# Schematic.net
KiCad netlist of a schematic drawn in Altium Designer
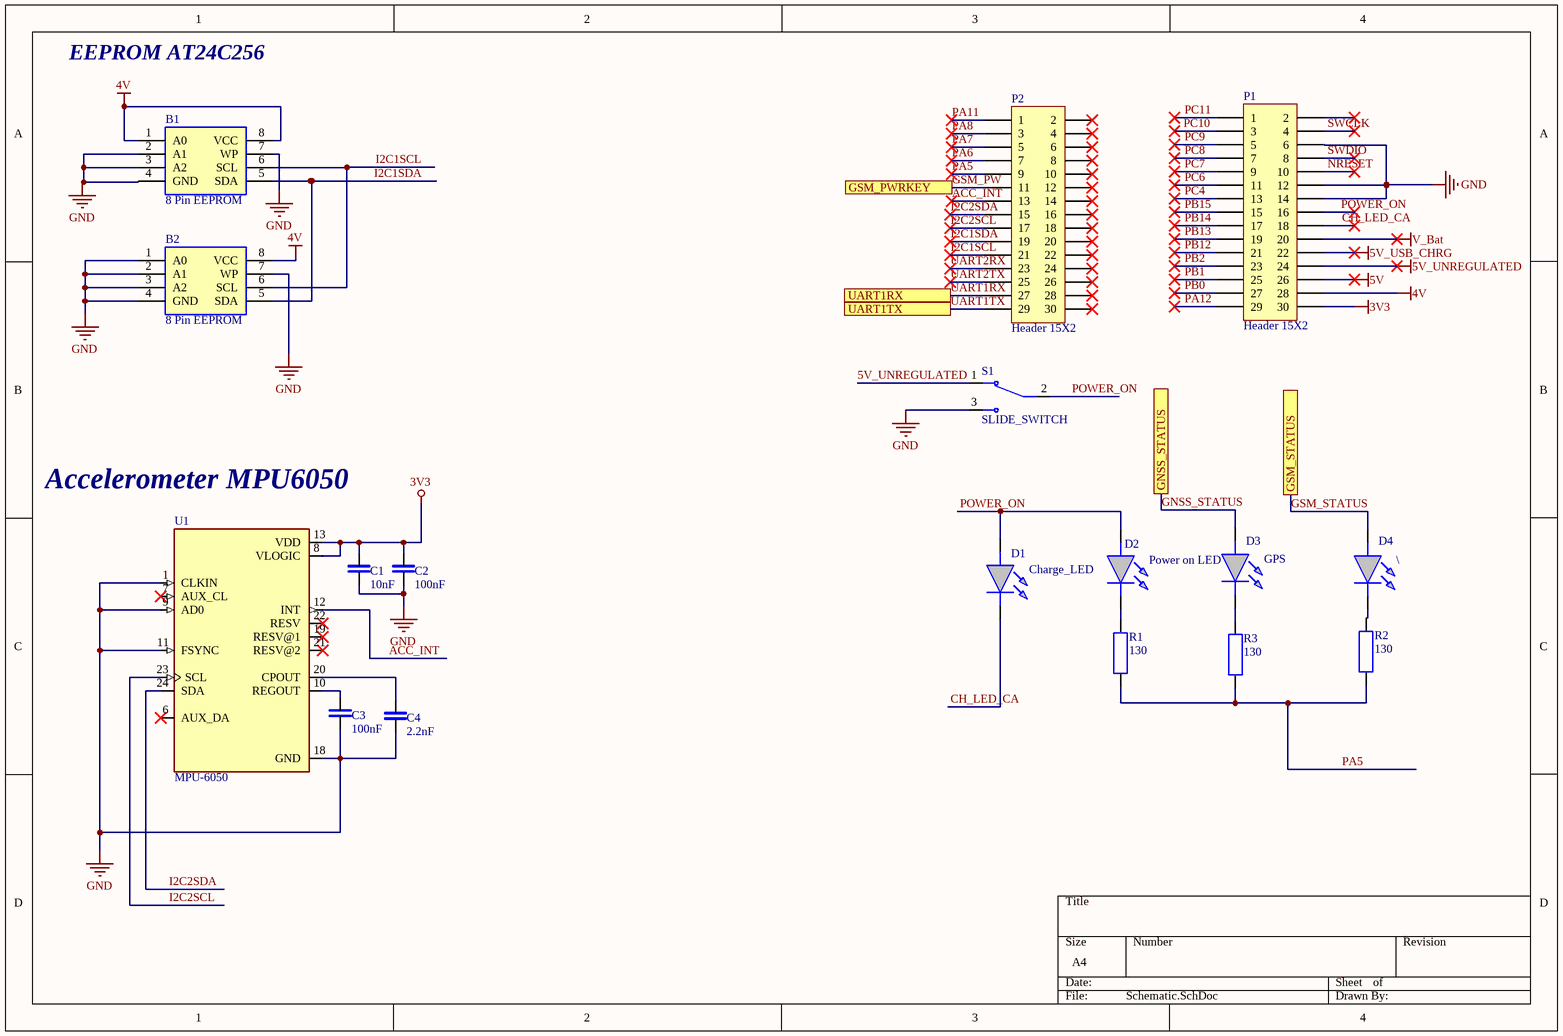
[diagram p0: Schematic.SchDoc]

(export (version "E")
  (design (tool "Eeschema 10.0.6"))
  (components
    (comp (ref "B1")
      (value "8 Pin EEPROM")
      (footprint "AT24C256")
      (fields
        (field (name "MANUFACTURER_PART_NUMBER") "AT24C256C-SSHL-T")
        (field (name "MOUSER PART NUMBER") "556-AT24C256C-SSHL-T")
      )
      (libsource (lib "IC") (part "AT24C256C"))
    )
    (comp (ref "B2")
      (value "8 Pin EEPROM")
      (footprint "AT24C256")
      (fields
        (field (name "MANUFACTURER_PART_NUMBER") "AT24C256C-SSHL-T")
        (field (name "MOUSER PART NUMBER") "556-AT24C256C-SSHL-T")
      )
      (libsource (lib "IC") (part "AT24C256C"))
    )
    (comp (ref "C1")
      (value "10nF")
      (footprint "CAP_0805")
      (fields (field (name "MP") "LD051A270KAB2A"))
      (libsource (lib "Passive_Components") (part "SMT_CAP"))
    )
    (comp (ref "C2")
      (value "100nF")
      (footprint "CAP_0805")
      (fields (field (name "MP") "LD051A270KAB2A"))
      (libsource (lib "Passive_Components") (part "SMT_CAP"))
    )
    (comp (ref "C3")
      (value "100nF")
      (footprint "CAP_0805")
      (fields (field (name "MP") "LD051A270KAB2A"))
      (libsource (lib "Passive_Components") (part "SMT_CAP"))
    )
    (comp (ref "C4")
      (value "2.2nF")
      (footprint "CAP_0805")
      (fields (field (name "MP") "LD051A270KAB2A"))
      (libsource (lib "Passive_Components") (part "SMT_CAP"))
    )
    (comp (ref "D1")
      (value "Charge_LED")
      (footprint "LED_0805")
      (fields
        (field (name "MANUFACTURER_PART_NUMBER") "HSMH-C170")
        (field (name "MOUSER PART NUMBER") "630-HSMH-C170")
      )
      (libsource (lib "Diodes") (part "LED"))
    )
    (comp (ref "D2")
      (value "Power on LED")
      (footprint "LED_0805")
      (fields
        (field (name "MANUFACTURER_PART_NUMBER") "HSMH-C170")
        (field (name "MOUSER PART NUMBER") "630-HSMH-C170")
      )
      (libsource (lib "Diodes") (part "LED"))
    )
    (comp (ref "D3")
      (value "GPS")
      (footprint "LED_0805")
      (fields
        (field (name "MANUFACTURER_PART_NUMBER") "HSMH-C170")
        (field (name "MOUSER PART NUMBER") "630-HSMH-C170")
      )
      (libsource (lib "Diodes") (part "LED"))
    )
    (comp (ref "D4")
      (value "\\")
      (footprint "LED_0805")
      (fields
        (field (name "MANUFACTURER_PART_NUMBER") "HSMH-C170")
        (field (name "MOUSER PART NUMBER") "630-HSMH-C170")
      )
      (libsource (lib "Diodes") (part "LED"))
    )
    (comp (ref "P1")
      (value "Header 15X2")
      (footprint "HDR2X15")
      (description "Header, 15-Pin, Dual row")
      (fields (field (name "PUBLISHER") "Altium Limited"))
      (libsource (lib "Miscellaneous Connectors") (part "Header 15X2"))
    )
    (comp (ref "P2")
      (value "Header 15X2")
      (footprint "HDR2X15")
      (description "Header, 15-Pin, Dual row")
      (fields (field (name "PUBLISHER") "Altium Limited"))
      (libsource (lib "Miscellaneous Connectors") (part "Header 15X2"))
    )
    (comp (ref "R1")
      (value "130")
      (footprint "RES_0805")
      (fields
        (field (name "MP") "2-2176053-0")
        (field (name "TOLERANCE") "1%")
        (field (name "MF") "TE Connectivity")
      )
      (libsource (lib "Passive_Components") (part "SMT_RES"))
    )
    (comp (ref "R2")
      (value "130")
      (footprint "RES_0805")
      (fields
        (field (name "MP") "2-2176053-0")
        (field (name "TOLERANCE") "1%")
        (field (name "MF") "TE Connectivity")
      )
      (libsource (lib "Passive_Components") (part "SMT_RES"))
    )
    (comp (ref "R3")
      (value "130")
      (footprint "RES_0805")
      (fields
        (field (name "MP") "2-2176053-0")
        (field (name "TOLERANCE") "1%")
        (field (name "MF") "TE Connectivity")
      )
      (libsource (lib "Passive_Components") (part "SMT_RES"))
    )
    (comp (ref "S1")
      (value "SLIDE_SWITCH")
      (footprint "SLIDE_SWITCH_BIG")
      (fields (field (name "MP") "500SSP1S2M2QEA"))
      (libsource (lib "Extras") (part "SLIDE_SWITCH_BIG"))
    )
    (comp (ref "U1")
      (value "MPU-6050")
      (footprint "MPU_6050")
      (fields (field (name "MF") "TDK InvenSense"))
      (libsource (lib "IC") (part "MPU-6050"))
    )
  )
  (nets
    (net (code "2") (name "/ACC_INT") (class "Default")
      (node (ref "P2") (pin "13") (pinfunction "13_13") (pintype "passive"))
      (node (ref "U1") (pin "12") (pinfunction "INT_12") (pintype "output"))
    )
    (net (code "3") (name "/CH_LED_CA") (class "Default")
      (node (ref "D1") (pin "1") (pinfunction "K_1") (pintype "passive"))
      (node (ref "P1") (pin "18") (pinfunction "18_18") (pintype "passive"))
    )
    (net (code "4") (name "/GNSS_STATUS") (class "Default")
      (node (ref "D3") (pin "2") (pinfunction "A_2") (pintype "passive"))
    )
    (net (code "5") (name "/GSM_PW") (class "Default")
      (node (ref "P2") (pin "11") (pinfunction "11_11") (pintype "passive"))
    )
    (net (code "6") (name "/GSM_STATUS") (class "Default")
      (node (ref "D4") (pin "2") (pinfunction "A_2") (pintype "passive"))
    )
    (net (code "7") (name "/I2C1SCL") (class "Default")
      (node (ref "B1") (pin "6") (pinfunction "SCL_6") (pintype "passive"))
      (node (ref "B2") (pin "6") (pinfunction "SCL_6") (pintype "passive"))
      (node (ref "P2") (pin "21") (pinfunction "21_21") (pintype "passive"))
    )
    (net (code "8") (name "/I2C1SDA") (class "Default")
      (node (ref "B1") (pin "5") (pinfunction "SDA_5") (pintype "passive"))
      (node (ref "B2") (pin "5") (pinfunction "SDA_5") (pintype "passive"))
      (node (ref "P2") (pin "19") (pinfunction "19_19") (pintype "passive"))
    )
    (net (code "9") (name "/I2C2SCL") (class "Default")
      (node (ref "P2") (pin "17") (pinfunction "17_17") (pintype "passive"))
      (node (ref "U1") (pin "23") (pinfunction "SCL_23") (pintype "input"))
    )
    (net (code "10") (name "/I2C2SDA") (class "Default")
      (node (ref "P2") (pin "15") (pinfunction "15_15") (pintype "passive"))
      (node (ref "U1") (pin "24") (pinfunction "SDA_24") (pintype "bidirectional"))
    )
    (net (code "11") (name "/NRESET") (class "Default")
      (node (ref "P1") (pin "10") (pinfunction "10_10") (pintype "passive+no_connect"))
    )
    (net (code "12") (name "/PA5") (class "Default")
      (node (ref "P2") (pin "9") (pinfunction "9_9") (pintype "passive"))
      (node (ref "R1") (pin "1") (pinfunction "1_1") (pintype "passive"))
      (node (ref "R2") (pin "1") (pinfunction "1_1") (pintype "passive"))
      (node (ref "R3") (pin "1") (pinfunction "1_1") (pintype "passive"))
    )
    (net (code "13") (name "/PA6") (class "Default")
      (node (ref "P2") (pin "7") (pinfunction "7_7") (pintype "passive+no_connect"))
    )
    (net (code "14") (name "/PA7") (class "Default")
      (node (ref "P2") (pin "5") (pinfunction "5_5") (pintype "passive+no_connect"))
    )
    (net (code "15") (name "/PA8") (class "Default")
      (node (ref "P2") (pin "3") (pinfunction "3_3") (pintype "passive+no_connect"))
    )
    (net (code "16") (name "/PA11") (class "Default")
      (node (ref "P2") (pin "1") (pinfunction "1_1") (pintype "passive+no_connect"))
    )
    (net (code "17") (name "/PA12") (class "Default")
      (node (ref "P1") (pin "29") (pinfunction "29_29") (pintype "passive+no_connect"))
    )
    (net (code "18") (name "/PB0") (class "Default")
      (node (ref "P1") (pin "27") (pinfunction "27_27") (pintype "passive+no_connect"))
    )
    (net (code "19") (name "/PB1") (class "Default")
      (node (ref "P1") (pin "25") (pinfunction "25_25") (pintype "passive+no_connect"))
    )
    (net (code "20") (name "/PB2") (class "Default")
      (node (ref "P1") (pin "23") (pinfunction "23_23") (pintype "passive+no_connect"))
    )
    (net (code "21") (name "/PB12") (class "Default")
      (node (ref "P1") (pin "21") (pinfunction "21_21") (pintype "passive+no_connect"))
    )
    (net (code "22") (name "/PB13") (class "Default")
      (node (ref "P1") (pin "19") (pinfunction "19_19") (pintype "passive+no_connect"))
    )
    (net (code "23") (name "/PB14") (class "Default")
      (node (ref "P1") (pin "17") (pinfunction "17_17") (pintype "passive+no_connect"))
    )
    (net (code "24") (name "/PB15") (class "Default")
      (node (ref "P1") (pin "15") (pinfunction "15_15") (pintype "passive+no_connect"))
    )
    (net (code "25") (name "/PC4") (class "Default")
      (node (ref "P1") (pin "13") (pinfunction "13_13") (pintype "passive+no_connect"))
    )
    (net (code "26") (name "/PC6") (class "Default")
      (node (ref "P1") (pin "11") (pinfunction "11_11") (pintype "passive+no_connect"))
    )
    (net (code "27") (name "/PC7") (class "Default")
      (node (ref "P1") (pin "9") (pinfunction "9_9") (pintype "passive+no_connect"))
    )
    (net (code "28") (name "/PC8") (class "Default")
      (node (ref "P1") (pin "7") (pinfunction "7_7") (pintype "passive+no_connect"))
    )
    (net (code "29") (name "/PC9") (class "Default")
      (node (ref "P1") (pin "5") (pinfunction "5_5") (pintype "passive+no_connect"))
    )
    (net (code "30") (name "/PC10") (class "Default")
      (node (ref "P1") (pin "3") (pinfunction "3_3") (pintype "passive+no_connect"))
    )
    (net (code "31") (name "/PC11") (class "Default")
      (node (ref "P1") (pin "1") (pinfunction "1_1") (pintype "passive+no_connect"))
    )
    (net (code "32") (name "/POWER_ON") (class "Default")
      (node (ref "D1") (pin "2") (pinfunction "A_2") (pintype "passive"))
      (node (ref "D2") (pin "2") (pinfunction "A_2") (pintype "passive"))
      (node (ref "P1") (pin "16") (pinfunction "16_16") (pintype "passive"))
      (node (ref "S1") (pin "2") (pinfunction "COM_2") (pintype "passive"))
    )
    (net (code "33") (name "/SWCLK") (class "Default")
      (node (ref "P1") (pin "4") (pinfunction "4_4") (pintype "passive+no_connect"))
    )
    (net (code "34") (name "/SWDIO") (class "Default")
      (node (ref "P1") (pin "8") (pinfunction "8_8") (pintype "passive+no_connect"))
    )
    (net (code "35") (name "/UART1RX") (class "Default")
      (node (ref "P2") (pin "27") (pinfunction "27_27") (pintype "passive"))
    )
    (net (code "36") (name "/UART1TX") (class "Default")
      (node (ref "P2") (pin "29") (pinfunction "29_29") (pintype "passive"))
    )
    (net (code "37") (name "/UART2RX") (class "Default")
      (node (ref "P2") (pin "23") (pinfunction "23_23") (pintype "passive+no_connect"))
    )
    (net (code "38") (name "/UART2TX") (class "Default")
      (node (ref "P2") (pin "25") (pinfunction "25_25") (pintype "passive+no_connect"))
    )
    (net (code "39") (name "3V3") (class "Default")
      (node (ref "C1") (pin "2") (pinfunction "2_2") (pintype "passive"))
      (node (ref "C2") (pin "2") (pinfunction "2_2") (pintype "passive"))
      (node (ref "P1") (pin "30") (pinfunction "30_30") (pintype "passive"))
      (node (ref "U1") (pin "13") (pinfunction "VDD_13") (pintype "power_in"))
      (node (ref "U1") (pin "8") (pinfunction "VLOGIC_8") (pintype "power_in"))
    )
    (net (code "40") (name "4V") (class "Default")
      (node (ref "B1") (pin "1") (pinfunction "A0_1") (pintype "passive"))
      (node (ref "B1") (pin "8") (pinfunction "VCC_8") (pintype "passive"))
      (node (ref "B2") (pin "8") (pinfunction "VCC_8") (pintype "passive"))
      (node (ref "P1") (pin "28") (pinfunction "28_28") (pintype "passive"))
    )
    (net (code "41") (name "5V") (class "Default")
      (node (ref "P1") (pin "26") (pinfunction "26_26") (pintype "passive"))
    )
    (net (code "42") (name "5V_UNREGULATED") (class "Default")
      (node (ref "P1") (pin "24") (pinfunction "24_24") (pintype "passive"))
      (node (ref "S1") (pin "1") (pinfunction "NC_1") (pintype "passive"))
    )
    (net (code "43") (name "5V_USB_CHRG") (class "Default")
      (node (ref "P1") (pin "22") (pinfunction "22_22") (pintype "passive"))
    )
    (net (code "44") (name "GND") (class "Default")
      (node (ref "B1") (pin "2") (pinfunction "A1_2") (pintype "passive"))
      (node (ref "B1") (pin "3") (pinfunction "A2_3") (pintype "passive"))
      (node (ref "B1") (pin "4") (pinfunction "GND_4") (pintype "passive"))
      (node (ref "B1") (pin "7") (pinfunction "WP_7") (pintype "passive"))
      (node (ref "B2") (pin "1") (pinfunction "A0_1") (pintype "passive"))
      (node (ref "B2") (pin "2") (pinfunction "A1_2") (pintype "passive"))
      (node (ref "B2") (pin "3") (pinfunction "A2_3") (pintype "passive"))
      (node (ref "B2") (pin "4") (pinfunction "GND_4") (pintype "passive"))
      (node (ref "B2") (pin "7") (pinfunction "WP_7") (pintype "passive"))
      (node (ref "C1") (pin "1") (pinfunction "1_1") (pintype "passive"))
      (node (ref "C2") (pin "1") (pinfunction "1_1") (pintype "passive"))
      (node (ref "C3") (pin "1") (pinfunction "1_1") (pintype "passive"))
      (node (ref "C4") (pin "1") (pinfunction "1_1") (pintype "passive"))
      (node (ref "P1") (pin "12") (pinfunction "12_12") (pintype "passive"))
      (node (ref "P1") (pin "14") (pinfunction "14_14") (pintype "passive"))
      (node (ref "P1") (pin "6") (pinfunction "6_6") (pintype "passive"))
      (node (ref "S1") (pin "3") (pinfunction "NO_3") (pintype "passive"))
      (node (ref "U1") (pin "1") (pinfunction "CLKIN_1") (pintype "input"))
      (node (ref "U1") (pin "11") (pinfunction "FSYNC_11") (pintype "input"))
      (node (ref "U1") (pin "18") (pinfunction "GND_18") (pintype "power_in"))
      (node (ref "U1") (pin "9") (pinfunction "AD0_9") (pintype "input"))
    )
    (net (code "45") (name "Net-(D2-K)") (class "Default")
      (node (ref "D2") (pin "1") (pinfunction "K_1") (pintype "passive"))
      (node (ref "R1") (pin "2") (pinfunction "2_2") (pintype "passive"))
    )
    (net (code "46") (name "Net-(D3-K)") (class "Default")
      (node (ref "D3") (pin "1") (pinfunction "K_1") (pintype "passive"))
      (node (ref "R3") (pin "2") (pinfunction "2_2") (pintype "passive"))
    )
    (net (code "47") (name "Net-(D4-K)") (class "Default")
      (node (ref "D4") (pin "1") (pinfunction "K_1") (pintype "passive"))
      (node (ref "R2") (pin "2") (pinfunction "2_2") (pintype "passive"))
    )
    (net (code "48") (name "Net-(U1-CPOUT)") (class "Default")
      (node (ref "C4") (pin "2") (pinfunction "2_2") (pintype "passive"))
      (node (ref "U1") (pin "20") (pinfunction "CPOUT_20") (pintype "passive"))
    )
    (net (code "49") (name "Net-(U1-REGOUT)") (class "Default")
      (node (ref "C3") (pin "2") (pinfunction "2_2") (pintype "passive"))
      (node (ref "U1") (pin "10") (pinfunction "REGOUT_10") (pintype "passive"))
    )
    (net (code "50") (name "V_Bat") (class "Default")
      (node (ref "P1") (pin "20") (pinfunction "20_20") (pintype "passive"))
    )
    (net (code "51") (name "unconnected-(P1-Pad2)") (class "Default")
      (node (ref "P1") (pin "2") (pinfunction "2_2") (pintype "passive+no_connect"))
    )
    (net (code "52") (name "unconnected-(P2-Pad2)") (class "Default")
      (node (ref "P2") (pin "2") (pinfunction "2_2") (pintype "passive+no_connect"))
    )
    (net (code "53") (name "unconnected-(P2-Pad4)") (class "Default")
      (node (ref "P2") (pin "4") (pinfunction "4_4") (pintype "passive+no_connect"))
    )
    (net (code "54") (name "unconnected-(P2-Pad6)") (class "Default")
      (node (ref "P2") (pin "6") (pinfunction "6_6") (pintype "passive+no_connect"))
    )
    (net (code "55") (name "unconnected-(P2-Pad8)") (class "Default")
      (node (ref "P2") (pin "8") (pinfunction "8_8") (pintype "passive+no_connect"))
    )
    (net (code "56") (name "unconnected-(P2-Pad10)") (class "Default")
      (node (ref "P2") (pin "10") (pinfunction "10_10") (pintype "passive+no_connect"))
    )
    (net (code "57") (name "unconnected-(P2-Pad12)") (class "Default")
      (node (ref "P2") (pin "12") (pinfunction "12_12") (pintype "passive+no_connect"))
    )
    (net (code "58") (name "unconnected-(P2-Pad14)") (class "Default")
      (node (ref "P2") (pin "14") (pinfunction "14_14") (pintype "passive+no_connect"))
    )
    (net (code "59") (name "unconnected-(P2-Pad16)") (class "Default")
      (node (ref "P2") (pin "16") (pinfunction "16_16") (pintype "passive+no_connect"))
    )
    (net (code "60") (name "unconnected-(P2-Pad18)") (class "Default")
      (node (ref "P2") (pin "18") (pinfunction "18_18") (pintype "passive+no_connect"))
    )
    (net (code "61") (name "unconnected-(P2-Pad20)") (class "Default")
      (node (ref "P2") (pin "20") (pinfunction "20_20") (pintype "passive+no_connect"))
    )
    (net (code "62") (name "unconnected-(P2-Pad22)") (class "Default")
      (node (ref "P2") (pin "22") (pinfunction "22_22") (pintype "passive+no_connect"))
    )
    (net (code "63") (name "unconnected-(P2-Pad24)") (class "Default")
      (node (ref "P2") (pin "24") (pinfunction "24_24") (pintype "passive+no_connect"))
    )
    (net (code "64") (name "unconnected-(P2-Pad26)") (class "Default")
      (node (ref "P2") (pin "26") (pinfunction "26_26") (pintype "passive+no_connect"))
    )
    (net (code "65") (name "unconnected-(P2-Pad28)") (class "Default")
      (node (ref "P2") (pin "28") (pinfunction "28_28") (pintype "passive+no_connect"))
    )
    (net (code "66") (name "unconnected-(P2-Pad30)") (class "Default")
      (node (ref "P2") (pin "30") (pinfunction "30_30") (pintype "passive+no_connect"))
    )
    (net (code "67") (name "unconnected-(U1-AUX_CL-Pad7)") (class "Default")
      (node (ref "U1") (pin "7") (pinfunction "AUX_CL_7") (pintype "input+no_connect"))
    )
    (net (code "68") (name "unconnected-(U1-AUX_DA-Pad6)") (class "Default")
      (node (ref "U1") (pin "6") (pinfunction "AUX_DA_6") (pintype "bidirectional+no_connect"))
    )
    (net (code "69") (name "unconnected-(U1-RESV-Pad22)") (class "Default")
      (node (ref "U1") (pin "22") (pinfunction "RESV_22") (pintype "passive+no_connect"))
    )
    (net (code "70") (name "unconnected-(U1-RESV@1-Pad19)") (class "Default")
      (node (ref "U1") (pin "19") (pinfunction "RESV@1_19") (pintype "passive+no_connect"))
    )
    (net (code "71") (name "unconnected-(U1-RESV@2-Pad21)") (class "Default")
      (node (ref "U1") (pin "21") (pinfunction "RESV@2_21") (pintype "passive+no_connect"))
    )
  )
)
